# Ex_Build_System_Lights.net
KiCad netlist of a schematic drawn in EAGLE
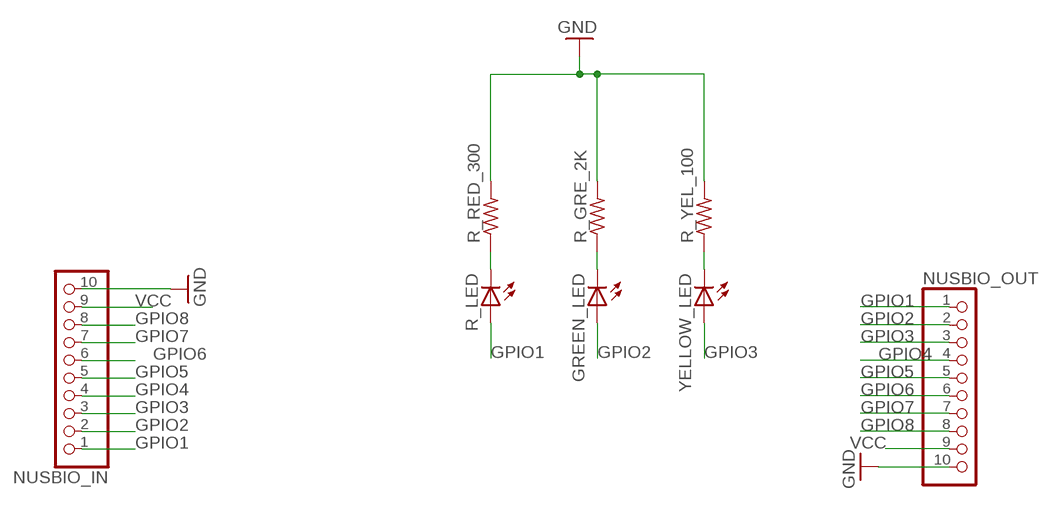
[diagram p0: schematic, sheet 1]

(export (version "E")
  (design (tool "Eeschema 10.0.6"))
  (components
    (comp (ref "GREEN_LED")
      (value "LED5MM")
      (footprint "eagle-import:LED5MM")
      (libsource (lib "eagle-import") (part "LED5MM"))
    )
    (comp (ref "NUSBIO_IN")
      (value "PINHD-1X10")
      (footprint "eagle-import:1X10-BIG")
      (libsource (lib "eagle-import") (part "PINHD-1X10"))
    )
    (comp (ref "NUSBIO_OUT")
      (value "PINHD-1X10")
      (footprint "eagle-import:1X10-BIG")
      (libsource (lib "eagle-import") (part "PINHD-1X10"))
    )
    (comp (ref "R_GRE_2K")
      (value "R-US_R0805")
      (footprint "eagle-import:R0805")
      (libsource (lib "eagle-import") (part "R-US_R0805"))
    )
    (comp (ref "R_LED")
      (value "LED5MM")
      (footprint "eagle-import:LED5MM")
      (libsource (lib "eagle-import") (part "LED5MM"))
    )
    (comp (ref "R_RED_300")
      (value "R-US_R0805")
      (footprint "eagle-import:R0805")
      (libsource (lib "eagle-import") (part "R-US_R0805"))
    )
    (comp (ref "R_YEL_100")
      (value "R-US_R0805")
      (footprint "eagle-import:R0805")
      (libsource (lib "eagle-import") (part "R-US_R0805"))
    )
    (comp (ref "YELLOW_LED")
      (value "LED5MM")
      (footprint "eagle-import:LED5MM")
      (libsource (lib "eagle-import") (part "LED5MM"))
    )
  )
  (nets
    (net (code "1") (name "/GPIO1") (class "Default")
      (node (ref "NUSBIO_IN") (pin "1") (pinfunction "1_1") (pintype "passive"))
      (node (ref "NUSBIO_OUT") (pin "1") (pinfunction "1_1") (pintype "passive"))
      (node (ref "R_LED") (pin "A") (pinfunction "A_A") (pintype "passive"))
    )
    (net (code "2") (name "/GPIO2") (class "Default")
      (node (ref "GREEN_LED") (pin "A") (pinfunction "A_A") (pintype "passive"))
      (node (ref "NUSBIO_IN") (pin "2") (pinfunction "2_2") (pintype "passive"))
      (node (ref "NUSBIO_OUT") (pin "2") (pinfunction "2_2") (pintype "passive"))
    )
    (net (code "3") (name "/GPIO3") (class "Default")
      (node (ref "NUSBIO_IN") (pin "3") (pinfunction "3_3") (pintype "passive"))
      (node (ref "NUSBIO_OUT") (pin "3") (pinfunction "3_3") (pintype "passive"))
      (node (ref "YELLOW_LED") (pin "A") (pinfunction "A_A") (pintype "passive"))
    )
    (net (code "4") (name "/GPIO4") (class "Default")
      (node (ref "NUSBIO_IN") (pin "4") (pinfunction "4_4") (pintype "passive"))
      (node (ref "NUSBIO_OUT") (pin "4") (pinfunction "4_4") (pintype "passive"))
    )
    (net (code "5") (name "/GPIO5") (class "Default")
      (node (ref "NUSBIO_IN") (pin "5") (pinfunction "5_5") (pintype "passive"))
      (node (ref "NUSBIO_OUT") (pin "5") (pinfunction "5_5") (pintype "passive"))
    )
    (net (code "6") (name "/GPIO6") (class "Default")
      (node (ref "NUSBIO_IN") (pin "6") (pinfunction "6_6") (pintype "passive"))
      (node (ref "NUSBIO_OUT") (pin "6") (pinfunction "6_6") (pintype "passive"))
    )
    (net (code "7") (name "/GPIO7") (class "Default")
      (node (ref "NUSBIO_IN") (pin "7") (pinfunction "7_7") (pintype "passive"))
      (node (ref "NUSBIO_OUT") (pin "7") (pinfunction "7_7") (pintype "passive"))
    )
    (net (code "8") (name "/GPIO8") (class "Default")
      (node (ref "NUSBIO_IN") (pin "8") (pinfunction "8_8") (pintype "passive"))
      (node (ref "NUSBIO_OUT") (pin "8") (pinfunction "8_8") (pintype "passive"))
    )
    (net (code "9") (name "/VCC") (class "Default")
      (node (ref "NUSBIO_IN") (pin "9") (pinfunction "9_9") (pintype "passive"))
      (node (ref "NUSBIO_OUT") (pin "9") (pinfunction "9_9") (pintype "passive"))
    )
    (net (code "10") (name "GND") (class "Default")
      (node (ref "NUSBIO_IN") (pin "10") (pinfunction "10_10") (pintype "passive"))
      (node (ref "NUSBIO_OUT") (pin "10") (pinfunction "10_10") (pintype "passive"))
      (node (ref "R_GRE_2K") (pin "2") (pinfunction "2_2") (pintype "passive"))
      (node (ref "R_RED_300") (pin "2") (pinfunction "2_2") (pintype "passive"))
      (node (ref "R_YEL_100") (pin "2") (pinfunction "2_2") (pintype "passive"))
    )
    (net (code "11") (name "Net-(GREEN_LED-C)") (class "Default")
      (node (ref "GREEN_LED") (pin "K") (pinfunction "C_K") (pintype "passive"))
      (node (ref "R_GRE_2K") (pin "1") (pinfunction "1_1") (pintype "passive"))
    )
    (net (code "12") (name "Net-(R_LED-C)") (class "Default")
      (node (ref "R_LED") (pin "K") (pinfunction "C_K") (pintype "passive"))
      (node (ref "R_RED_300") (pin "1") (pinfunction "1_1") (pintype "passive"))
    )
    (net (code "13") (name "Net-(YELLOW_LED-C)") (class "Default")
      (node (ref "R_YEL_100") (pin "1") (pinfunction "1_1") (pintype "passive"))
      (node (ref "YELLOW_LED") (pin "K") (pinfunction "C_K") (pintype "passive"))
    )
  )
)
